# Altium_Schematic_Rev3.net
KiCad netlist of a schematic drawn in Altium Designer
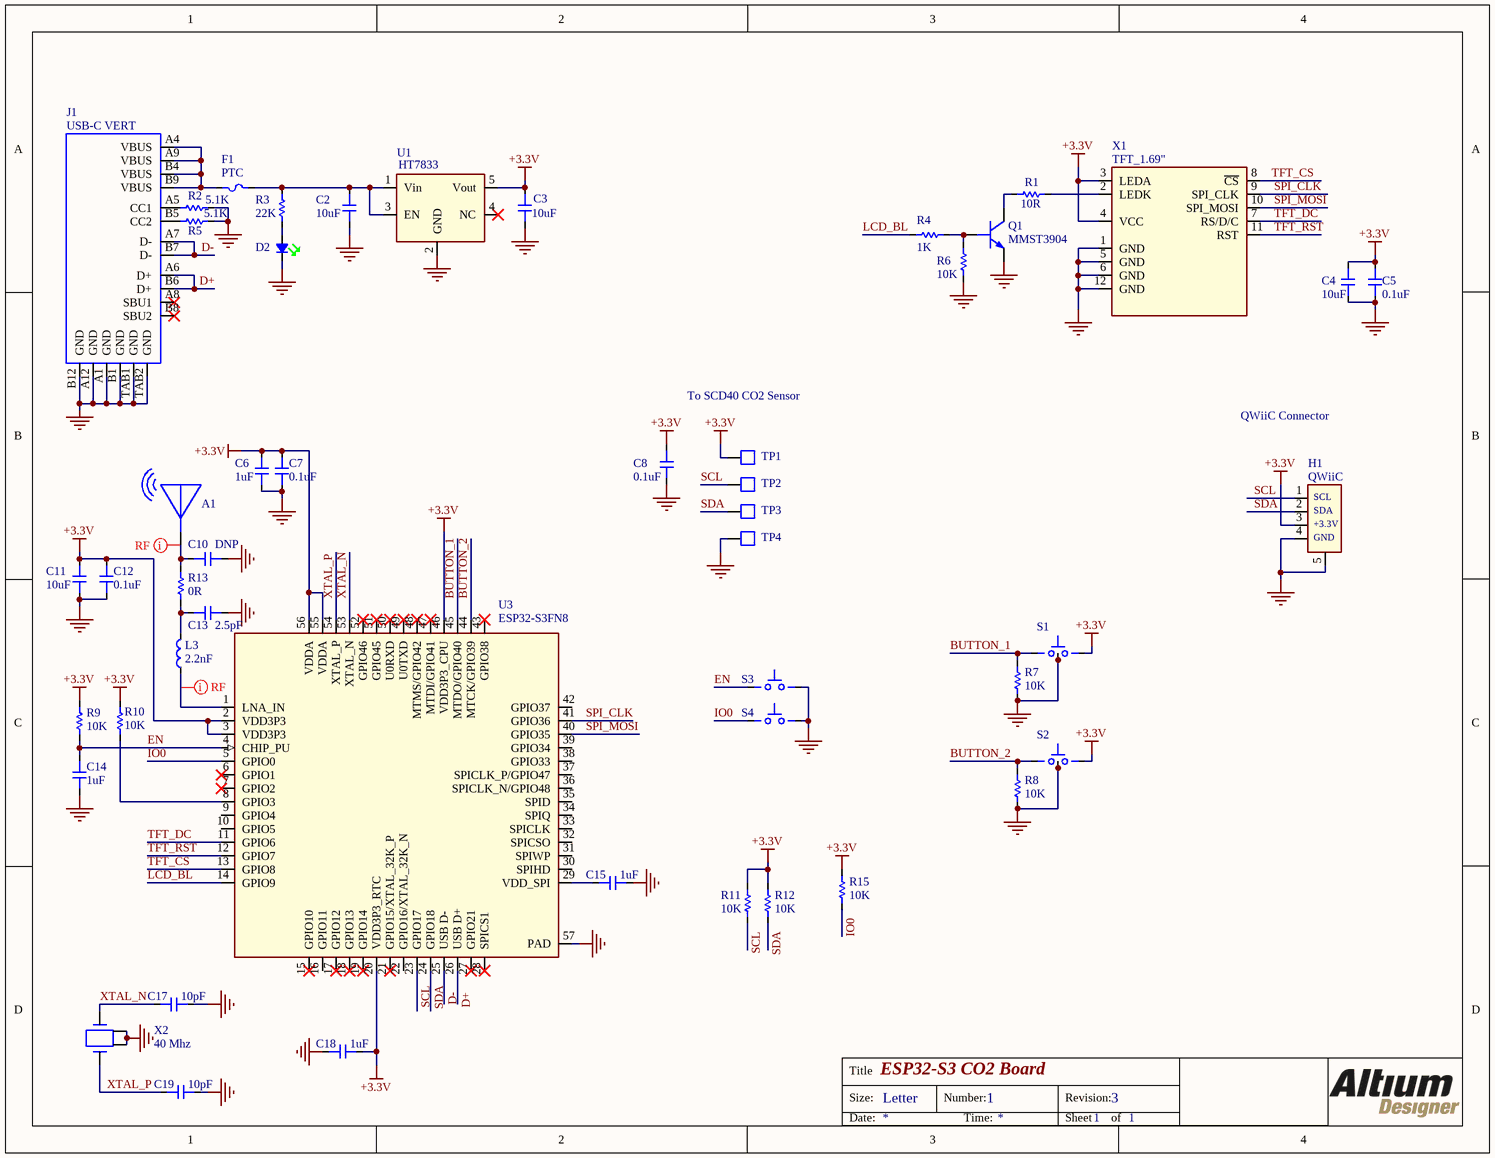
[diagram p0: Altium_Schematic_Rev3.SchDoc]

(export (version "E")
  (design (tool "Eeschema 10.0.6"))
  (components
    (comp (ref "A1")
      (value "ANT3216LL00R2400A")
      (footprint "ANT3216LL00R2400A")
      (description "Antenna Chip 2.4Gig")
      (fields (field (name "MANUFACTURER") "YAGEO"))
      (libsource (lib "MAR") (part "ANT3216LL00R2400A"))
    )
    (comp (ref "C2")
      (value "10uF")
      (footprint "CAPC2012X140N")
      (description "CAP 10uF 50V 0805")
      (libsource (lib "MAR") (part "CAP_0805"))
    )
    (comp (ref "C3")
      (value "10uF")
      (footprint "CAPC2012X140N")
      (description "CAP 10uF 50V 0805")
      (libsource (lib "MAR") (part "CAP_0805"))
    )
    (comp (ref "C4")
      (value "10uF")
      (footprint "CAPC2012X140N")
      (description "CAP 10uF 0805")
      (libsource (lib "MAR") (part "CAP_0805"))
    )
    (comp (ref "C5")
      (value "0.1uF")
      (footprint "CAPC1608X09L")
      (description "CAP 0.1uF 0603")
      (libsource (lib "MAR") (part "CAP_0603"))
    )
    (comp (ref "C6")
      (value "1uF")
      (footprint "CAPC1608X09L")
      (description "CAP 1uF 0603")
      (libsource (lib "MAR") (part "CAP_0603"))
    )
    (comp (ref "C7")
      (value "0.1uF")
      (footprint "CAPC1608X09L")
      (description "CAP 0.1uF 0603")
      (libsource (lib "MAR") (part "CAP_0603"))
    )
    (comp (ref "C8")
      (value "0.1uF")
      (footprint "CAPC1608X09L")
      (description "CAP 0.1uF 0603")
      (libsource (lib "MAR") (part "CAP_0603"))
    )
    (comp (ref "C10")
      (value "DNP")
      (footprint "CAPC1005X56N")
      (description "CAP DNP 0402")
      (libsource (lib "MAR") (part "CAP_0402"))
    )
    (comp (ref "C11")
      (value "10uF")
      (footprint "CAPC2012X140N")
      (description "CAP 10uF 50V 0805")
      (libsource (lib "MAR") (part "CAP_0805"))
    )
    (comp (ref "C12")
      (value "0.1uF")
      (footprint "CAPC1005X56N")
      (description "CAP 0.1uF 0402")
      (libsource (lib "MAR") (part "CAP_0402"))
    )
    (comp (ref "C13")
      (value "2.5pF")
      (footprint "CAPC1005X56N")
      (description "CAP 2.5pF 0402")
      (libsource (lib "MAR") (part "CAP_0402"))
    )
    (comp (ref "C14")
      (value "1uF")
      (footprint "CAPC1005X56N")
      (description "CAP 1uF 0402")
      (libsource (lib "MAR") (part "CAP_0402"))
    )
    (comp (ref "C15")
      (value "1uF")
      (footprint "CAPC1005X56N")
      (description "CAP 1uF 0402")
      (libsource (lib "MAR") (part "CAP_0402"))
    )
    (comp (ref "C17")
      (value "10pF")
      (footprint "CAPC1005X56N")
      (description "CAP 10pF 0402")
      (libsource (lib "MAR") (part "CAP_0402"))
    )
    (comp (ref "C18")
      (value "1uF")
      (footprint "CAPC1608X09L")
      (description "CAP 1uF 0603")
      (libsource (lib "MAR") (part "CAP_0603"))
    )
    (comp (ref "C19")
      (value "10pF")
      (footprint "CAPC1005X56N")
      (description "CAP 10pF 0402")
      (libsource (lib "MAR") (part "CAP_0402"))
    )
    (comp (ref "D2")
      (value "Green Led")
      (footprint "LED1005X40N-Green")
      (description "LED Green 0402")
      (fields (field (name "PART_NUMBER") "C74338"))
      (libsource (lib "MAR") (part "LED_0402_SMALL_GREEN"))
    )
    (comp (ref "F1")
      (value "PTC")
      (footprint "RESC1608X06L (0603 FOOTPRINT)")
      (description "PTC FUSE 0.5mA hold, 1A trip 0603")
      (fields (field (name "MANUFACTURER") "JDT Fuse") (field (name "PART_NUMBER") "C2982257"))
      (libsource (lib "MAR") (part "PTC_FUSE_0603"))
    )
    (comp (ref "H1")
      (value "QWiiC")
      (footprint "SM04B-SRSS-TB")
      (description "CONN HEADER 4POS .100 R/A QWIIC")
      (fields (field (name "MANUFACTURER") "JST") (field (name "PART_NUMBER") "PRT-14417"))
      (libsource (lib "MAR") (part "SM04B-SRSS-TB"))
    )
    (comp (ref "J1")
      (value "USB-C VERT")
      (footprint "TYPE-C-31-G-06")
      (description "CONN RECPT USB-C Vertical")
      (fields (field (name "MANUFACTURER") "Korean Elec") (field (name "PART_NUMBER") "C283539"))
      (libsource (lib "MAR") (part "USB-C_VERT"))
    )
    (comp (ref "L3")
      (value "2.2nF")
      (footprint "INDC1005X40L")
      (description "Inductor 2.2nF")
      (libsource (lib "MAR") (part "Inductor"))
    )
    (comp (ref "Q1")
      (value "MMST3904")
      (footprint "SC-70")
      (description "TRANSISTOR NPN GP 40V SC-70")
      (fields (field (name "MANUFACTURER") "Changjiang") (field (name "PART_NUMBER") "C54879"))
      (libsource (lib "MAR") (part "MMST3904"))
    )
    (comp (ref "R1")
      (value "10R")
      (footprint "RESC1005X40L (0402 FOOTPRINT)")
      (description "RES 10R 0402")
      (libsource (lib "MAR") (part "RES_0402"))
    )
    (comp (ref "R2")
      (value "5.1K")
      (footprint "RESC1005X40L (0402 FOOTPRINT)")
      (description "RES 5.1K 0402")
      (libsource (lib "MAR") (part "RES_0402"))
    )
    (comp (ref "R3")
      (value "22K")
      (footprint "RESC1005X40L (0402 FOOTPRINT)")
      (description "RES 22K 0402")
      (libsource (lib "MAR") (part "RES_0402"))
    )
    (comp (ref "R4")
      (value "1K")
      (footprint "RESC1005X40L (0402 FOOTPRINT)")
      (description "RES 1K 0402")
      (libsource (lib "MAR") (part "RES_0402"))
    )
    (comp (ref "R5")
      (value "5.1K")
      (footprint "RESC1005X40L (0402 FOOTPRINT)")
      (description "RES 5.1K 0402")
      (libsource (lib "MAR") (part "RES_0402"))
    )
    (comp (ref "R6")
      (value "10K")
      (footprint "RESC1005X40L (0402 FOOTPRINT)")
      (description "RES 10K 0402")
      (libsource (lib "MAR") (part "RES_0402"))
    )
    (comp (ref "R7")
      (value "10K")
      (footprint "RESC1005X40L (0402 FOOTPRINT)")
      (description "RES 10K 0402")
      (libsource (lib "MAR") (part "RES_0402"))
    )
    (comp (ref "R8")
      (value "10K")
      (footprint "RESC1005X40L (0402 FOOTPRINT)")
      (description "RES 10K 0402")
      (libsource (lib "MAR") (part "RES_0402"))
    )
    (comp (ref "R9")
      (value "10K")
      (footprint "RESC1005X40L (0402 FOOTPRINT)")
      (description "RES 10K 0402")
      (libsource (lib "MAR") (part "RES_0402"))
    )
    (comp (ref "R10")
      (value "10K")
      (footprint "RESC1005X40L (0402 FOOTPRINT)")
      (description "RES 10K 0402")
      (libsource (lib "MAR") (part "RES_0402"))
    )
    (comp (ref "R11")
      (value "10K")
      (footprint "RESC1005X40L (0402 FOOTPRINT)")
      (description "RES 10K 0402")
      (libsource (lib "MAR") (part "RES_0402"))
    )
    (comp (ref "R12")
      (value "10K")
      (footprint "RESC1005X40L (0402 FOOTPRINT)")
      (description "RES 10K 0402")
      (libsource (lib "MAR") (part "RES_0402"))
    )
    (comp (ref "R13")
      (value "0R")
      (footprint "RESC1005X40L (0402 FOOTPRINT)")
      (description "RES 0R 0402")
      (libsource (lib "MAR") (part "RES_0402"))
    )
    (comp (ref "R15")
      (value "10K")
      (footprint "RESC1005X40L (0402 FOOTPRINT)")
      (description "RES 10K 0402")
      (libsource (lib "MAR") (part "RES_0402"))
    )
    (comp (ref "S1")
      (value "Push")
      (footprint "1TS003A-1600-3500A")
      (description "SWITCH TACTILE R/A MICRO")
      (fields (field (name "PART_NUMBER") "C255805") (field (name "MANUFACTURER") "HYP"))
      (libsource (lib "MAR") (part "SWITCH TACTILE R/A_MICRO"))
    )
    (comp (ref "S2")
      (value "Push")
      (footprint "1TS003A-1600-3500A")
      (description "SWITCH TACTILE R/A MICRO")
      (fields (field (name "PART_NUMBER") "C255805") (field (name "MANUFACTURER") "HYP"))
      (libsource (lib "MAR") (part "SWITCH TACTILE R/A_MICRO"))
    )
    (comp (ref "S3")
      (value "~")
      (footprint "TL1015AF160QG")
      (description "SWITCH MOMENTARY")
      (fields (field (name "PART_NUMBER") "TL1015AF160QG"))
      (libsource (lib "MAR") (part "TL1015AF160QG"))
    )
    (comp (ref "S4")
      (value "~")
      (footprint "TL1015AF160QG")
      (description "SWITCH MOMENTARY")
      (fields (field (name "PART_NUMBER") "TL1015AF160QG"))
      (libsource (lib "MAR") (part "TL1015AF160QG"))
    )
    (comp (ref "TP1")
      (value "Test Point, 1mm Top Layer")
      (footprint "TP100TL")
      (libsource (lib "MAR") (part "Test Point, 1mm Top Layer"))
    )
    (comp (ref "TP2")
      (value "Test Point, 1mm Top Layer")
      (footprint "TP100TL")
      (libsource (lib "MAR") (part "Test Point, 1mm Top Layer"))
    )
    (comp (ref "TP3")
      (value "Test Point, 1mm Top Layer")
      (footprint "TP100TL")
      (libsource (lib "MAR") (part "Test Point, 1mm Top Layer"))
    )
    (comp (ref "TP4")
      (value "Test Point, 1mm Top Layer")
      (footprint "TP100TL")
      (libsource (lib "MAR") (part "Test Point, 1mm Top Layer"))
    )
    (comp (ref "U1")
      (value "HT7833")
      (footprint "SOT95P280X144-5N")
      (description "IC LDO 3.3V 0.5A SOT23-5")
      (fields (field (name "MANUFACTURER") "Holtek") (field (name "PART_NUMBER") "C164106"))
      (libsource (lib "MAR") (part "HT7833"))
    )
    (comp (ref "U3")
      (value "ESP32-S3FN8")
      (footprint "QFN56_0.4mm pitch - Rev2")
      (description "WIFI/Bluetooth, 8M PSRAM, QFN-56 7x7")
      (fields (field (name "MANUFACTURER") "Espressif"))
      (libsource (lib "MAR") (part "ESP32-S3"))
    )
    (comp (ref "X1")
      (value "TFT_1.69\"")
      (footprint "TFT_GLASS 1.69 INCH SPI")
      (description "1.69 INCH TFT SPI GLASS COLOR ROUNDED CORNERS")
      (fields (field (name "PART_NUMBER") "LH169TIG01"))
      (libsource (lib "MAR") (part "TFT_GLASS 1.69 INCH COLOR SPI"))
    )
    (comp (ref "X2")
      (value "40 Mhz")
      (footprint "OSC20X16")
      (description "CRYSTAL 40MHZ 10PF SMD")
      (fields (field (name "PART_NUMBER") "ECS-400-10-37B2-CKM") (field (name "MANUFACTURER") "ECS"))
      (libsource (lib "MAR") (part "40Mhz"))
    )
  )
  (nets
    (net (code "1") (name "+3.3V") (class "Default")
      (node (ref "C11") (pin "1") (pintype "passive"))
      (node (ref "C12") (pin "1") (pintype "passive"))
      (node (ref "C18") (pin "2") (pintype "passive"))
      (node (ref "C3") (pin "1") (pintype "passive"))
      (node (ref "C4") (pin "1") (pintype "passive"))
      (node (ref "C5") (pin "1") (pintype "passive"))
      (node (ref "C6") (pin "1") (pintype "passive"))
      (node (ref "C7") (pin "1") (pintype "passive"))
      (node (ref "C8") (pin "1") (pintype "passive"))
      (node (ref "H1") (pin "3") (pintype "passive"))
      (node (ref "R10") (pin "1") (pintype "passive"))
      (node (ref "R11") (pin "1") (pintype "passive"))
      (node (ref "R12") (pin "1") (pintype "passive"))
      (node (ref "R15") (pin "2") (pintype "passive"))
      (node (ref "R9") (pin "2") (pintype "passive"))
      (node (ref "S1") (pin "2") (pinfunction "B_2") (pintype "passive"))
      (node (ref "S2") (pin "2") (pinfunction "B_2") (pintype "passive"))
      (node (ref "TP1") (pin "1") (pinfunction "1_1") (pintype "passive"))
      (node (ref "U1") (pin "5") (pinfunction "Vout_5") (pintype "passive"))
      (node (ref "U3") (pin "2") (pinfunction "VDD3P3_2") (pintype "power_in"))
      (node (ref "U3") (pin "20") (pinfunction "VDD3P3_RTC_20") (pintype "power_in"))
      (node (ref "U3") (pin "3") (pinfunction "VDD3P3_3") (pintype "power_in"))
      (node (ref "U3") (pin "46") (pinfunction "VDD3P3_CPU_46") (pintype "power_in"))
      (node (ref "U3") (pin "55") (pinfunction "VDDA_55") (pintype "power_in"))
      (node (ref "U3") (pin "56") (pinfunction "VDDA_56") (pintype "power_in"))
      (node (ref "X1") (pin "3") (pinfunction "LEDA_3") (pintype "passive"))
      (node (ref "X1") (pin "4") (pinfunction "VCC_4") (pintype "power_in"))
    )
    (net (code "2") (name "/BUTTON_1") (class "Default")
      (node (ref "R7") (pin "2") (pintype "passive"))
      (node (ref "S1") (pin "1") (pinfunction "A_1") (pintype "passive"))
      (node (ref "U3") (pin "45") (pinfunction "MTDO/GPIO40_45") (pintype "passive"))
    )
    (net (code "3") (name "/BUTTON_2") (class "Default")
      (node (ref "R8") (pin "2") (pintype "passive"))
      (node (ref "S2") (pin "1") (pinfunction "A_1") (pintype "passive"))
      (node (ref "U3") (pin "44") (pinfunction "MTCK/GPIO39_44") (pintype "passive"))
    )
    (net (code "4") (name "/D+") (class "Default")
      (node (ref "J1") (pin "A6") (pinfunction "D+_A6") (pintype "power_in"))
      (node (ref "J1") (pin "B6") (pinfunction "D+_B6") (pintype "power_in"))
      (node (ref "U3") (pin "26") (pinfunction "USB_D+_26") (pintype "passive"))
    )
    (net (code "5") (name "/D-") (class "Default")
      (node (ref "J1") (pin "A7") (pinfunction "D-_A7") (pintype "power_in"))
      (node (ref "J1") (pin "B7") (pinfunction "D-_B7") (pintype "power_in"))
      (node (ref "U3") (pin "25") (pinfunction "USB_D-_25") (pintype "passive"))
    )
    (net (code "6") (name "/EN") (class "Default")
      (node (ref "C14") (pin "1") (pintype "passive"))
      (node (ref "R9") (pin "1") (pintype "passive"))
      (node (ref "S3") (pin "1") (pinfunction "A_1") (pintype "passive"))
      (node (ref "U3") (pin "4") (pinfunction "CHIP_PU_4") (pintype "input"))
    )
    (net (code "7") (name "/IO0") (class "Default")
      (node (ref "R15") (pin "1") (pintype "passive"))
      (node (ref "S4") (pin "1") (pinfunction "A_1") (pintype "passive"))
      (node (ref "U3") (pin "5") (pinfunction "GPIO0_5") (pintype "passive"))
    )
    (net (code "8") (name "/LCD_BL") (class "Default")
      (node (ref "R4") (pin "2") (pintype "passive"))
      (node (ref "U3") (pin "14") (pinfunction "GPIO9_14") (pintype "passive"))
    )
    (net (code "9") (name "/SCL") (class "Default")
      (node (ref "H1") (pin "1") (pintype "passive"))
      (node (ref "R11") (pin "2") (pintype "passive"))
      (node (ref "TP2") (pin "1") (pinfunction "1_1") (pintype "passive"))
      (node (ref "U3") (pin "23") (pinfunction "GPIO17_23") (pintype "passive"))
    )
    (net (code "10") (name "/SDA") (class "Default")
      (node (ref "H1") (pin "2") (pintype "passive"))
      (node (ref "R12") (pin "2") (pintype "passive"))
      (node (ref "TP3") (pin "1") (pinfunction "1_1") (pintype "passive"))
      (node (ref "U3") (pin "24") (pinfunction "GPIO18_24") (pintype "passive"))
    )
    (net (code "11") (name "/SPI_CLK") (class "Default")
      (node (ref "U3") (pin "41") (pinfunction "GPIO36_41") (pintype "passive"))
      (node (ref "X1") (pin "9") (pinfunction "SPI_CLK_9") (pintype "passive"))
    )
    (net (code "12") (name "/SPI_MOSI") (class "Default")
      (node (ref "U3") (pin "40") (pinfunction "GPIO35_40") (pintype "passive"))
      (node (ref "X1") (pin "10") (pinfunction "SPI_MOSI_10") (pintype "passive"))
    )
    (net (code "13") (name "/TFT_CS") (class "Default")
      (node (ref "U3") (pin "13") (pinfunction "GPIO8_13") (pintype "passive"))
      (node (ref "X1") (pin "8") (pinfunction "~{CS}_8") (pintype "passive"))
    )
    (net (code "14") (name "/TFT_DC") (class "Default")
      (node (ref "U3") (pin "11") (pinfunction "GPIO6_11") (pintype "passive"))
      (node (ref "X1") (pin "7") (pinfunction "RS/D/C_7") (pintype "passive"))
    )
    (net (code "15") (name "/TFT_RST") (class "Default")
      (node (ref "U3") (pin "12") (pinfunction "GPIO7_12") (pintype "passive"))
      (node (ref "X1") (pin "11") (pinfunction "RST_11") (pintype "passive"))
    )
    (net (code "16") (name "/XTAL_N") (class "Default")
      (node (ref "C17") (pin "1") (pintype "passive"))
      (node (ref "U3") (pin "53") (pinfunction "XTAL_N_53") (pintype "passive"))
      (node (ref "X2") (pin "3") (pinfunction "3_3") (pintype "passive"))
    )
    (net (code "17") (name "/XTAL_P") (class "Default")
      (node (ref "C19") (pin "1") (pintype "passive"))
      (node (ref "U3") (pin "54") (pinfunction "XTAL_P_54") (pintype "passive"))
      (node (ref "X2") (pin "1") (pinfunction "1_1") (pintype "passive"))
    )
    (net (code "18") (name "GND") (class "Default")
      (node (ref "C10") (pin "2") (pintype "passive"))
      (node (ref "C11") (pin "2") (pintype "passive"))
      (node (ref "C12") (pin "2") (pintype "passive"))
      (node (ref "C13") (pin "2") (pintype "passive"))
      (node (ref "C14") (pin "2") (pintype "passive"))
      (node (ref "C15") (pin "2") (pintype "passive"))
      (node (ref "C17") (pin "2") (pintype "passive"))
      (node (ref "C18") (pin "1") (pintype "passive"))
      (node (ref "C19") (pin "2") (pintype "passive"))
      (node (ref "C2") (pin "2") (pintype "passive"))
      (node (ref "C3") (pin "2") (pintype "passive"))
      (node (ref "C4") (pin "2") (pintype "passive"))
      (node (ref "C5") (pin "2") (pintype "passive"))
      (node (ref "C6") (pin "2") (pintype "passive"))
      (node (ref "C7") (pin "2") (pintype "passive"))
      (node (ref "C8") (pin "2") (pintype "passive"))
      (node (ref "D2") (pin "1") (pintype "passive"))
      (node (ref "H1") (pin "4") (pintype "passive"))
      (node (ref "H1") (pin "5") (pintype "passive"))
      (node (ref "J1") (pin "A1") (pinfunction "GND_A1") (pintype "power_in"))
      (node (ref "J1") (pin "A12") (pinfunction "GND_A12") (pintype "power_in"))
      (node (ref "J1") (pin "B1") (pinfunction "GND_B1") (pintype "power_in"))
      (node (ref "J1") (pin "B12") (pinfunction "GND_B12") (pintype "passive"))
      (node (ref "J1") (pin "TAB1") (pinfunction "GND_TAB1") (pintype "passive"))
      (node (ref "J1") (pin "TAB2") (pinfunction "GND_TAB2") (pintype "passive"))
      (node (ref "Q1") (pin "2") (pinfunction "E_2") (pintype "passive"))
      (node (ref "R2") (pin "1") (pintype "passive"))
      (node (ref "R5") (pin "1") (pintype "passive"))
      (node (ref "R6") (pin "2") (pintype "passive"))
      (node (ref "R7") (pin "1") (pintype "passive"))
      (node (ref "R8") (pin "1") (pintype "passive"))
      (node (ref "S1") (pin "3") (pinfunction "3_3") (pintype "passive"))
      (node (ref "S1") (pin "4") (pinfunction "4_4") (pintype "passive"))
      (node (ref "S2") (pin "3") (pinfunction "3_3") (pintype "passive"))
      (node (ref "S2") (pin "4") (pinfunction "4_4") (pintype "passive"))
      (node (ref "S3") (pin "2") (pinfunction "B_2") (pintype "passive"))
      (node (ref "S4") (pin "2") (pinfunction "B_2") (pintype "passive"))
      (node (ref "TP4") (pin "1") (pinfunction "1_1") (pintype "passive"))
      (node (ref "U1") (pin "2") (pinfunction "GND_2") (pintype "power_in"))
      (node (ref "U3") (pin "57") (pinfunction "PAD_57") (pintype "power_in"))
      (node (ref "X1") (pin "1") (pinfunction "GND_1") (pintype "power_in"))
      (node (ref "X1") (pin "12") (pinfunction "GND_12") (pintype "power_in"))
      (node (ref "X1") (pin "5") (pinfunction "GND_5") (pintype "power_in"))
      (node (ref "X1") (pin "6") (pinfunction "GND_6") (pintype "power_in"))
      (node (ref "X2") (pin "2") (pinfunction "2_2") (pintype "power_in"))
      (node (ref "X2") (pin "4") (pinfunction "4_4") (pintype "power_in"))
    )
    (net (code "19") (name "Net-(A1-Pad1)") (class "Default")
      (node (ref "A1") (pin "1") (pintype "passive"))
      (node (ref "C10") (pin "1") (pintype "passive"))
      (node (ref "R13") (pin "2") (pintype "passive"))
    )
    (net (code "20") (name "Net-(C13-Pad1)") (class "Default")
      (node (ref "C13") (pin "1") (pintype "passive"))
      (node (ref "L3") (pin "1") (pinfunction "1_1") (pintype "passive"))
      (node (ref "R13") (pin "1") (pintype "passive"))
    )
    (net (code "21") (name "Net-(D2-Pad2)") (class "Default")
      (node (ref "D2") (pin "2") (pintype "passive"))
      (node (ref "R3") (pin "1") (pintype "passive"))
    )
    (net (code "22") (name "Net-(F1-Pad2)") (class "Default")
      (node (ref "F1") (pin "2") (pintype "passive"))
      (node (ref "J1") (pin "A4") (pinfunction "VBUS_A4") (pintype "passive"))
      (node (ref "J1") (pin "A9") (pinfunction "VBUS_A9") (pintype "power_in"))
      (node (ref "J1") (pin "B4") (pinfunction "VBUS_B4") (pintype "power_in"))
      (node (ref "J1") (pin "B9") (pinfunction "VBUS_B9") (pintype "passive"))
    )
    (net (code "23") (name "Net-(J1-CC1)") (class "Default")
      (node (ref "J1") (pin "A5") (pinfunction "CC1_A5") (pintype "power_in"))
      (node (ref "R2") (pin "2") (pintype "passive"))
    )
    (net (code "24") (name "Net-(J1-CC2)") (class "Default")
      (node (ref "J1") (pin "B5") (pinfunction "CC2_B5") (pintype "power_in"))
      (node (ref "R5") (pin "2") (pintype "passive"))
    )
    (net (code "25") (name "Net-(Q1-B)") (class "Default")
      (node (ref "Q1") (pin "1") (pinfunction "B_1") (pintype "passive"))
      (node (ref "R4") (pin "1") (pintype "passive"))
      (node (ref "R6") (pin "1") (pintype "passive"))
    )
    (net (code "26") (name "Net-(Q1-C)") (class "Default")
      (node (ref "Q1") (pin "3") (pinfunction "C_3") (pintype "passive"))
      (node (ref "R1") (pin "2") (pintype "passive"))
    )
    (net (code "27") (name "Net-(U1-EN)") (class "Default")
      (node (ref "C2") (pin "1") (pintype "passive"))
      (node (ref "F1") (pin "1") (pintype "passive"))
      (node (ref "R3") (pin "2") (pintype "passive"))
      (node (ref "U1") (pin "1") (pinfunction "Vin_1") (pintype "passive"))
      (node (ref "U1") (pin "3") (pinfunction "EN_3") (pintype "passive"))
    )
    (net (code "28") (name "Net-(U3-GPIO3)") (class "Default")
      (node (ref "R10") (pin "2") (pintype "passive"))
      (node (ref "U3") (pin "8") (pinfunction "GPIO3_8") (pintype "passive"))
    )
    (net (code "29") (name "Net-(U3-LNA_IN)") (class "Default")
      (node (ref "L3") (pin "2") (pinfunction "2_2") (pintype "passive"))
      (node (ref "U3") (pin "1") (pinfunction "LNA_IN_1") (pintype "passive"))
    )
    (net (code "30") (name "Net-(U3-VDD_SPI)") (class "Default")
      (node (ref "C15") (pin "1") (pintype "passive"))
      (node (ref "U3") (pin "29") (pinfunction "VDD_SPI_29") (pintype "power_in"))
    )
    (net (code "31") (name "Net-(X1-LEDK)") (class "Default")
      (node (ref "R1") (pin "1") (pintype "passive"))
      (node (ref "X1") (pin "2") (pinfunction "LEDK_2") (pintype "passive"))
    )
    (net (code "32") (name "unconnected-(J1-SBU1-PadA8)") (class "Default")
      (node (ref "J1") (pin "A8") (pinfunction "SBU1_A8") (pintype "power_in+no_connect"))
    )
    (net (code "33") (name "unconnected-(J1-SBU2-PadB8)") (class "Default")
      (node (ref "J1") (pin "B8") (pinfunction "SBU2_B8") (pintype "power_in+no_connect"))
    )
    (net (code "34") (name "unconnected-(U1-NC-Pad4)") (class "Default")
      (node (ref "U1") (pin "4") (pinfunction "NC_4") (pintype "passive+no_connect"))
    )
    (net (code "35") (name "unconnected-(U3-GPIO1-Pad6)") (class "Default")
      (node (ref "U3") (pin "6") (pinfunction "GPIO1_6") (pintype "passive+no_connect"))
    )
    (net (code "36") (name "unconnected-(U3-GPIO2-Pad7)") (class "Default")
      (node (ref "U3") (pin "7") (pinfunction "GPIO2_7") (pintype "passive+no_connect"))
    )
    (net (code "37") (name "unconnected-(U3-GPIO4-Pad9)") (class "Default")
      (node (ref "U3") (pin "9") (pinfunction "GPIO4_9") (pintype "passive"))
    )
    (net (code "38") (name "unconnected-(U3-GPIO5-Pad10)") (class "Default")
      (node (ref "U3") (pin "10") (pinfunction "GPIO5_10") (pintype "passive"))
    )
    (net (code "39") (name "unconnected-(U3-GPIO10-Pad15)") (class "Default")
      (node (ref "U3") (pin "15") (pinfunction "GPIO10_15") (pintype "passive+no_connect"))
    )
    (net (code "40") (name "unconnected-(U3-GPIO11-Pad16)") (class "Default")
      (node (ref "U3") (pin "16") (pinfunction "GPIO11_16") (pintype "passive"))
    )
    (net (code "41") (name "unconnected-(U3-GPIO12-Pad17)") (class "Default")
      (node (ref "U3") (pin "17") (pinfunction "GPIO12_17") (pintype "passive+no_connect"))
    )
    (net (code "42") (name "unconnected-(U3-GPIO13-Pad18)") (class "Default")
      (node (ref "U3") (pin "18") (pinfunction "GPIO13_18") (pintype "passive+no_connect"))
    )
    (net (code "43") (name "unconnected-(U3-GPIO14-Pad19)") (class "Default")
      (node (ref "U3") (pin "19") (pinfunction "GPIO14_19") (pintype "passive+no_connect"))
    )
    (net (code "44") (name "unconnected-(U3-GPIO15{slash}XTAL_32K_P-Pad21)") (class "Default")
      (node (ref "U3") (pin "21") (pinfunction "GPIO15/XTAL_32K_P_21") (pintype "passive+no_connect"))
    )
    (net (code "45") (name "unconnected-(U3-GPIO16{slash}XTAL_32K_N-Pad22)") (class "Default")
      (node (ref "U3") (pin "22") (pinfunction "GPIO16/XTAL_32K_N_22") (pintype "passive"))
    )
    (net (code "46") (name "unconnected-(U3-GPIO21-Pad27)") (class "Default")
      (node (ref "U3") (pin "27") (pinfunction "GPIO21_27") (pintype "passive+no_connect"))
    )
    (net (code "47") (name "unconnected-(U3-GPIO33-Pad38)") (class "Default")
      (node (ref "U3") (pin "38") (pinfunction "GPIO33_38") (pintype "passive"))
    )
    (net (code "48") (name "unconnected-(U3-GPIO34-Pad39)") (class "Default")
      (node (ref "U3") (pin "39") (pinfunction "GPIO34_39") (pintype "passive"))
    )
    (net (code "49") (name "unconnected-(U3-GPIO37-Pad42)") (class "Default")
      (node (ref "U3") (pin "42") (pinfunction "GPIO37_42") (pintype "passive"))
    )
    (net (code "50") (name "unconnected-(U3-GPIO38-Pad43)") (class "Default")
      (node (ref "U3") (pin "43") (pinfunction "GPIO38_43") (pintype "passive+no_connect"))
    )
    (net (code "51") (name "unconnected-(U3-GPIO45-Pad51)") (class "Default")
      (node (ref "U3") (pin "51") (pinfunction "GPIO45_51") (pintype "passive+no_connect"))
    )
    (net (code "52") (name "unconnected-(U3-GPIO46-Pad52)") (class "Default")
      (node (ref "U3") (pin "52") (pinfunction "GPIO46_52") (pintype "passive+no_connect"))
    )
    (net (code "53") (name "unconnected-(U3-MTDI{slash}GPIO41-Pad47)") (class "Default")
      (node (ref "U3") (pin "47") (pinfunction "MTDI/GPIO41_47") (pintype "passive+no_connect"))
    )
    (net (code "54") (name "unconnected-(U3-MTMS{slash}GPIO42-Pad48)") (class "Default")
      (node (ref "U3") (pin "48") (pinfunction "MTMS/GPIO42_48") (pintype "passive+no_connect"))
    )
    (net (code "55") (name "unconnected-(U3-SPICLK-Pad33)") (class "Default")
      (node (ref "U3") (pin "33") (pinfunction "SPICLK_33") (pintype "passive"))
    )
    (net (code "56") (name "unconnected-(U3-SPICLK_N{slash}GPIO48-Pad36)") (class "Default")
      (node (ref "U3") (pin "36") (pinfunction "SPICLK_N/GPIO48_36") (pintype "passive"))
    )
    (net (code "57") (name "unconnected-(U3-SPICLK_P{slash}GPIO47-Pad37)") (class "Default")
      (node (ref "U3") (pin "37") (pinfunction "SPICLK_P/GPIO47_37") (pintype "passive"))
    )
    (net (code "58") (name "unconnected-(U3-SPICS1-Pad28)") (class "Default")
      (node (ref "U3") (pin "28") (pinfunction "SPICS1_28") (pintype "passive+no_connect"))
    )
    (net (code "59") (name "unconnected-(U3-SPICSO-Pad32)") (class "Default")
      (node (ref "U3") (pin "32") (pinfunction "SPICSO_32") (pintype "passive"))
    )
    (net (code "60") (name "unconnected-(U3-SPID-Pad35)") (class "Default")
      (node (ref "U3") (pin "35") (pinfunction "SPID_35") (pintype "passive"))
    )
    (net (code "61") (name "unconnected-(U3-SPIHD-Pad30)") (class "Default")
      (node (ref "U3") (pin "30") (pinfunction "SPIHD_30") (pintype "passive"))
    )
    (net (code "62") (name "unconnected-(U3-SPIQ-Pad34)") (class "Default")
      (node (ref "U3") (pin "34") (pinfunction "SPIQ_34") (pintype "passive"))
    )
    (net (code "63") (name "unconnected-(U3-SPIWP-Pad31)") (class "Default")
      (node (ref "U3") (pin "31") (pinfunction "SPIWP_31") (pintype "passive"))
    )
    (net (code "64") (name "unconnected-(U3-U0RXD-Pad50)") (class "Default")
      (node (ref "U3") (pin "50") (pinfunction "U0RXD_50") (pintype "passive+no_connect"))
    )
    (net (code "65") (name "unconnected-(U3-U0TXD-Pad49)") (class "Default")
      (node (ref "U3") (pin "49") (pinfunction "U0TXD_49") (pintype "passive+no_connect"))
    )
  )
)
